# sam7x-nrf.net
KiCad netlist of a schematic drawn in EAGLE
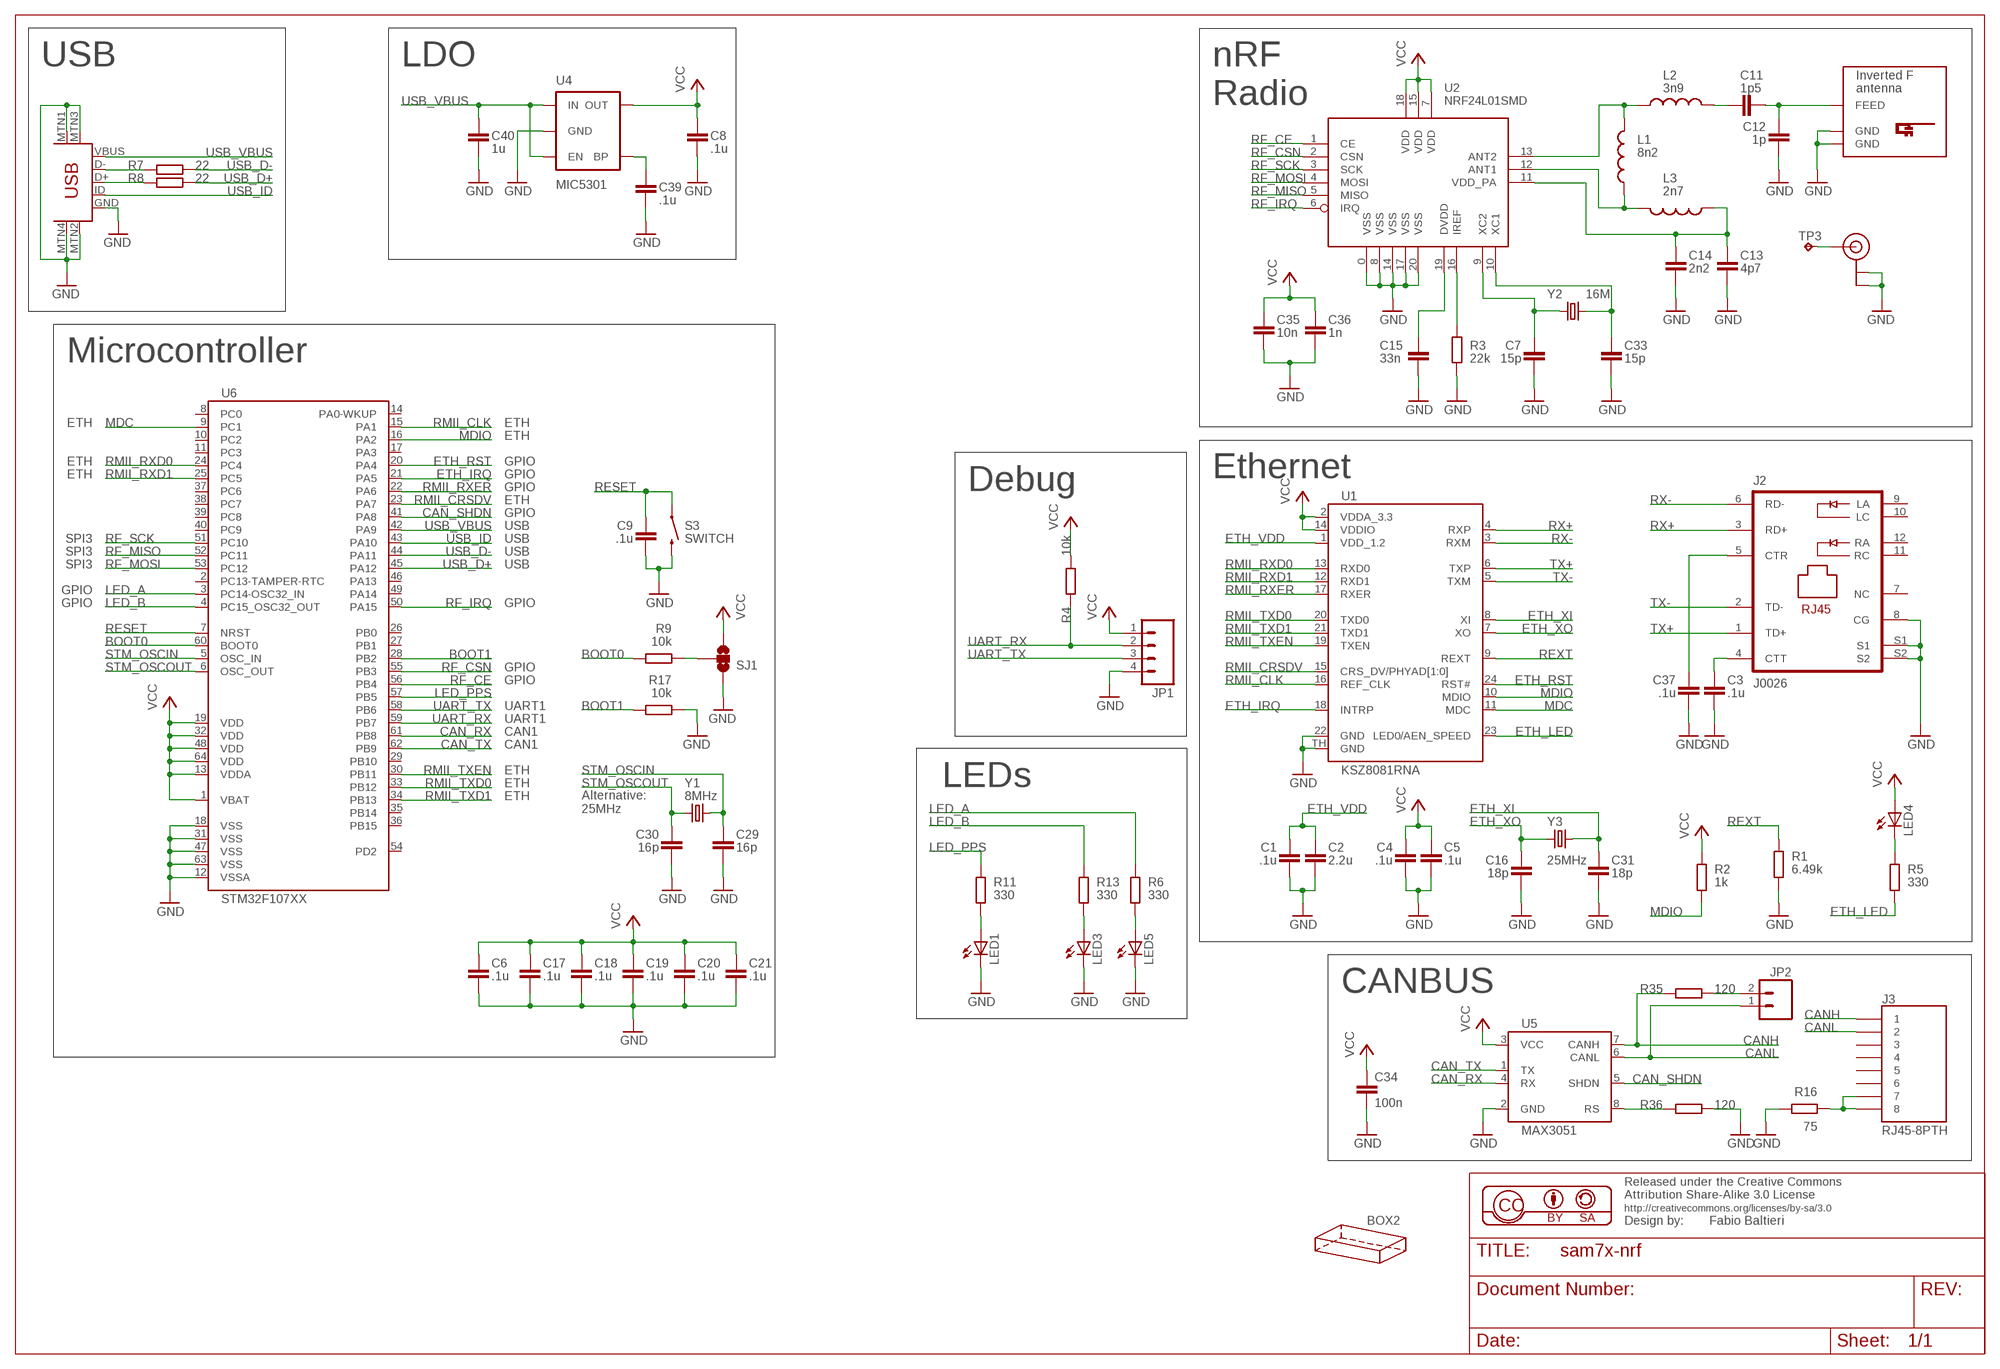
[diagram p0: schematic, sheet 1]

(export (version "E")
  (design (tool "Eeschema 10.0.6"))
  (components
    (comp (ref "BOX2")
      (value "HAMMOND-BOX-K")
      (footprint "eagle-import:1551K")
      (libsource (lib "eagle-import") (part "HAMMOND-BOX-K"))
    )
    (comp (ref "C1")
      (value ".1u")
      (footprint "eagle-import:C0603")
      (libsource (lib "eagle-import") (part "C-EUC0603"))
    )
    (comp (ref "C2")
      (value "2.2u")
      (footprint "eagle-import:C0603")
      (libsource (lib "eagle-import") (part "C-EUC0603"))
    )
    (comp (ref "C3")
      (value ".1u")
      (footprint "eagle-import:C0603")
      (libsource (lib "eagle-import") (part "C-EUC0603"))
    )
    (comp (ref "C4")
      (value ".1u")
      (footprint "eagle-import:C0603")
      (libsource (lib "eagle-import") (part "C-EUC0603"))
    )
    (comp (ref "C5")
      (value ".1u")
      (footprint "eagle-import:C0603")
      (libsource (lib "eagle-import") (part "C-EUC0603"))
    )
    (comp (ref "C6")
      (value ".1u")
      (footprint "eagle-import:C0603")
      (libsource (lib "eagle-import") (part "C-EUC0603"))
    )
    (comp (ref "C7")
      (value "15p")
      (footprint "eagle-import:C0603")
      (libsource (lib "eagle-import") (part "C-EUC0603"))
    )
    (comp (ref "C8")
      (value ".1u")
      (footprint "eagle-import:C0603")
      (libsource (lib "eagle-import") (part "C-EUC0603"))
    )
    (comp (ref "C9")
      (value ".1u")
      (footprint "eagle-import:C0603")
      (libsource (lib "eagle-import") (part "C-EUC0603"))
    )
    (comp (ref "C11")
      (value "1p5")
      (footprint "eagle-import:C0603")
      (libsource (lib "eagle-import") (part "C-EUC0603"))
    )
    (comp (ref "C12")
      (value "1p")
      (footprint "eagle-import:C0603")
      (libsource (lib "eagle-import") (part "C-EUC0603"))
    )
    (comp (ref "C13")
      (value "4p7")
      (footprint "eagle-import:C0603")
      (libsource (lib "eagle-import") (part "C-EUC0603"))
    )
    (comp (ref "C14")
      (value "2n2")
      (footprint "eagle-import:C0603")
      (libsource (lib "eagle-import") (part "C-EUC0603"))
    )
    (comp (ref "C15")
      (value "33n")
      (footprint "eagle-import:C0603")
      (libsource (lib "eagle-import") (part "C-EUC0603"))
    )
    (comp (ref "C16")
      (value "18p")
      (footprint "eagle-import:C0603")
      (libsource (lib "eagle-import") (part "C-EUC0603"))
    )
    (comp (ref "C17")
      (value ".1u")
      (footprint "eagle-import:C0603")
      (libsource (lib "eagle-import") (part "C-EUC0603"))
    )
    (comp (ref "C18")
      (value ".1u")
      (footprint "eagle-import:C0603")
      (libsource (lib "eagle-import") (part "C-EUC0603"))
    )
    (comp (ref "C19")
      (value ".1u")
      (footprint "eagle-import:C0603")
      (libsource (lib "eagle-import") (part "C-EUC0603"))
    )
    (comp (ref "C20")
      (value ".1u")
      (footprint "eagle-import:C0603")
      (libsource (lib "eagle-import") (part "C-EUC0603"))
    )
    (comp (ref "C21")
      (value ".1u")
      (footprint "eagle-import:C0603")
      (libsource (lib "eagle-import") (part "C-EUC0603"))
    )
    (comp (ref "C29")
      (value "16p")
      (footprint "eagle-import:C0603")
      (libsource (lib "eagle-import") (part "C-EUC0603"))
    )
    (comp (ref "C30")
      (value "16p")
      (footprint "eagle-import:C0603")
      (libsource (lib "eagle-import") (part "C-EUC0603"))
    )
    (comp (ref "C31")
      (value "18p")
      (footprint "eagle-import:C0603")
      (libsource (lib "eagle-import") (part "C-EUC0603"))
    )
    (comp (ref "C33")
      (value "15p")
      (footprint "eagle-import:C0603")
      (libsource (lib "eagle-import") (part "C-EUC0603"))
    )
    (comp (ref "C34")
      (value "100n")
      (footprint "eagle-import:C0603")
      (libsource (lib "eagle-import") (part "C-EUC0603"))
    )
    (comp (ref "C35")
      (value "10n")
      (footprint "eagle-import:C0603")
      (libsource (lib "eagle-import") (part "C-EUC0603"))
    )
    (comp (ref "C36")
      (value "1n")
      (footprint "eagle-import:C0603")
      (libsource (lib "eagle-import") (part "C-EUC0603"))
    )
    (comp (ref "C37")
      (value ".1u")
      (footprint "eagle-import:C0603")
      (libsource (lib "eagle-import") (part "C-EUC0603"))
    )
    (comp (ref "C39")
      (value ".1u")
      (footprint "eagle-import:C0603")
      (libsource (lib "eagle-import") (part "C-EUC0603"))
    )
    (comp (ref "C40")
      (value "1u")
      (footprint "eagle-import:C0603")
      (libsource (lib "eagle-import") (part "C-EUC0603"))
    )
    (comp (ref "J2")
      (value "J0026")
      (footprint "eagle-import:PJ-J0")
      (libsource (lib "eagle-import") (part "J0026"))
    )
    (comp (ref "J3")
      (value "RJ45-8PTH")
      (footprint "eagle-import:RJ45-8")
      (libsource (lib "eagle-import") (part "RJ45-8PTH"))
    )
    (comp (ref "JP1")
      (value "M04PTH")
      (footprint "eagle-import:1X04")
      (libsource (lib "eagle-import") (part "M04PTH"))
    )
    (comp (ref "JP2")
      (value "M02PTH")
      (footprint "eagle-import:1X02")
      (libsource (lib "eagle-import") (part "M02PTH"))
    )
    (comp (ref "L1")
      (value "8n2")
      (footprint "eagle-import:0603")
      (libsource (lib "eagle-import") (part "INDUCTOR0603"))
    )
    (comp (ref "L2")
      (value "3n9")
      (footprint "eagle-import:0603")
      (libsource (lib "eagle-import") (part "INDUCTOR0603"))
    )
    (comp (ref "L3")
      (value "2n7")
      (footprint "eagle-import:0603")
      (libsource (lib "eagle-import") (part "INDUCTOR0603"))
    )
    (comp (ref "LED1")
      (value "LEDCHIPLED_0805")
      (footprint "eagle-import:CHIPLED_0805")
      (libsource (lib "eagle-import") (part "LEDCHIPLED_0805"))
    )
    (comp (ref "LED3")
      (value "LEDCHIPLED_0805")
      (footprint "eagle-import:CHIPLED_0805")
      (libsource (lib "eagle-import") (part "LEDCHIPLED_0805"))
    )
    (comp (ref "LED4")
      (value "LEDCHIPLED_0805")
      (footprint "eagle-import:CHIPLED_0805")
      (libsource (lib "eagle-import") (part "LEDCHIPLED_0805"))
    )
    (comp (ref "LED5")
      (value "LEDCHIPLED_0805")
      (footprint "eagle-import:CHIPLED_0805")
      (libsource (lib "eagle-import") (part "LEDCHIPLED_0805"))
    )
    (comp (ref "R1")
      (value "6.49k")
      (footprint "eagle-import:R0603")
      (libsource (lib "eagle-import") (part "R-EU_R0603"))
    )
    (comp (ref "R2")
      (value "1k")
      (footprint "eagle-import:R0603")
      (libsource (lib "eagle-import") (part "R-EU_R0603"))
    )
    (comp (ref "R3")
      (value "22k")
      (footprint "eagle-import:R0603")
      (libsource (lib "eagle-import") (part "R-EU_R0603"))
    )
    (comp (ref "R4")
      (value "10k")
      (footprint "eagle-import:R0603")
      (libsource (lib "eagle-import") (part "R-EU_R0603"))
    )
    (comp (ref "R5")
      (value "330")
      (footprint "eagle-import:R0603")
      (libsource (lib "eagle-import") (part "R-EU_R0603"))
    )
    (comp (ref "R6")
      (value "330")
      (footprint "eagle-import:R0603")
      (libsource (lib "eagle-import") (part "R-EU_R0603"))
    )
    (comp (ref "R7")
      (value "22")
      (footprint "eagle-import:R0603")
      (libsource (lib "eagle-import") (part "R-EU_R0603"))
    )
    (comp (ref "R8")
      (value "22")
      (footprint "eagle-import:R0603")
      (libsource (lib "eagle-import") (part "R-EU_R0603"))
    )
    (comp (ref "R9")
      (value "10k")
      (footprint "eagle-import:R0603")
      (libsource (lib "eagle-import") (part "R-EU_R0603"))
    )
    (comp (ref "R11")
      (value "330")
      (footprint "eagle-import:R0603")
      (libsource (lib "eagle-import") (part "R-EU_R0603"))
    )
    (comp (ref "R13")
      (value "330")
      (footprint "eagle-import:R0603")
      (libsource (lib "eagle-import") (part "R-EU_R0603"))
    )
    (comp (ref "R16")
      (value "75")
      (footprint "eagle-import:R0805")
      (libsource (lib "eagle-import") (part "R-EU_R0805"))
    )
    (comp (ref "R17")
      (value "10k")
      (footprint "eagle-import:R0603")
      (libsource (lib "eagle-import") (part "R-EU_R0603"))
    )
    (comp (ref "R35")
      (value "120")
      (footprint "eagle-import:R0805")
      (libsource (lib "eagle-import") (part "R-EU_R0805"))
    )
    (comp (ref "R36")
      (value "120")
      (footprint "eagle-import:R0603")
      (libsource (lib "eagle-import") (part "R-EU_R0603"))
    )
    (comp (ref "S3")
      (value "SWITCH")
      (footprint "eagle-import:TACTILE_SWITCH_SMD")
      (libsource (lib "eagle-import") (part "SWITCH-MOMENTARY-2SMD"))
    )
    (comp (ref "SJ1")
      (value "SOLDERJUMPER_2WAYS")
      (footprint "eagle-import:SJ_3")
      (libsource (lib "eagle-import") (part "SOLDERJUMPER_2WAYS"))
    )
    (comp (ref "TP3")
      (value "TPTP08SQ")
      (footprint "eagle-import:TP08SQ")
      (libsource (lib "eagle-import") (part "TPTP08SQ"))
    )
    (comp (ref "U$4")
      (value "USB-MINIB-5PIN")
      (footprint "eagle-import:USB-MINIB")
      (libsource (lib "eagle-import") (part "USB-MINIB-5PIN"))
    )
    (comp (ref "U$5")
      (value "INVERTED_F_ANTENNA-2")
      (footprint "eagle-import:DN007-2")
      (libsource (lib "eagle-import") (part "INVERTED_F_ANTENNA-2"))
    )
    (comp (ref "U$6")
      (value "U.FL")
      (footprint "eagle-import:U.FL")
      (libsource (lib "eagle-import") (part "U.FL"))
    )
    (comp (ref "U1")
      (value "KSZ8081RNA")
      (footprint "eagle-import:QFN24")
      (libsource (lib "eagle-import") (part "KSZ8081"))
    )
    (comp (ref "U2")
      (value "NRF24L01SMD")
      (footprint "eagle-import:QFN20")
      (libsource (lib "eagle-import") (part "NRF24L01SMD"))
    )
    (comp (ref "U4")
      (value "MIC5301")
      (footprint "eagle-import:SOT23-5")
      (libsource (lib "eagle-import") (part "V_REG_LDOSMD"))
    )
    (comp (ref "U5")
      (value "MAX3051")
      (footprint "eagle-import:SO08")
      (libsource (lib "eagle-import") (part "MAX3051"))
    )
    (comp (ref "U6")
      (value "STM32F107XX")
      (footprint "eagle-import:LQFP64")
      (libsource (lib "eagle-import") (part "STM32F107XX"))
    )
    (comp (ref "Y1")
      (value "8MHz")
      (footprint "eagle-import:CRYSTAL-SMD-5X3")
      (libsource (lib "eagle-import") (part "CRYSTAL5X3"))
    )
    (comp (ref "Y2")
      (value "16M")
      (footprint "eagle-import:CRYSTAL-SMD-5X3")
      (libsource (lib "eagle-import") (part "CRYSTAL5X3"))
    )
    (comp (ref "Y3")
      (value "25MHz")
      (footprint "eagle-import:CRYSTAL-SMD-5X3")
      (libsource (lib "eagle-import") (part "CRYSTAL5X3"))
    )
  )
  (nets
    (net (code "1") (name "/BOOT0") (class "Default")
      (node (ref "R9") (pin "2") (pinfunction "2_2") (pintype "passive"))
      (node (ref "U6") (pin "60") (pinfunction "BOOT0_60") (pintype "bidirectional"))
    )
    (net (code "2") (name "/BOOT1") (class "Default")
      (node (ref "R17") (pin "2") (pinfunction "2_2") (pintype "passive"))
      (node (ref "U6") (pin "28") (pinfunction "PB2_28") (pintype "bidirectional"))
    )
    (net (code "3") (name "/CANH") (class "Default")
      (node (ref "J3") (pin "1") (pinfunction "1_1") (pintype "bidirectional"))
      (node (ref "R35") (pin "1") (pinfunction "1_1") (pintype "passive"))
      (node (ref "U5") (pin "7") (pinfunction "CANH_7") (pintype "bidirectional"))
    )
    (net (code "4") (name "/CANL") (class "Default")
      (node (ref "J3") (pin "2") (pinfunction "2_2") (pintype "bidirectional"))
      (node (ref "JP2") (pin "1") (pinfunction "1_1") (pintype "passive"))
      (node (ref "U5") (pin "6") (pinfunction "CANL_6") (pintype "bidirectional"))
    )
    (net (code "5") (name "/CAN_RX") (class "Default")
      (node (ref "U5") (pin "4") (pinfunction "RX_4") (pintype "bidirectional"))
      (node (ref "U6") (pin "61") (pinfunction "PB8_61") (pintype "bidirectional"))
    )
    (net (code "6") (name "/CAN_SHDN") (class "Default")
      (node (ref "U5") (pin "5") (pinfunction "SHDN_5") (pintype "bidirectional"))
      (node (ref "U6") (pin "41") (pinfunction "PA8_41") (pintype "bidirectional"))
    )
    (net (code "7") (name "/CAN_TX") (class "Default")
      (node (ref "U5") (pin "1") (pinfunction "TX_1") (pintype "bidirectional"))
      (node (ref "U6") (pin "62") (pinfunction "PB9_62") (pintype "bidirectional"))
    )
    (net (code "8") (name "/ETH_IRQ") (class "Default")
      (node (ref "U1") (pin "18") (pinfunction "INTRP_18") (pintype "bidirectional"))
      (node (ref "U6") (pin "21") (pinfunction "PA5_21") (pintype "bidirectional"))
    )
    (net (code "9") (name "/ETH_LED") (class "Default")
      (node (ref "R5") (pin "1") (pinfunction "1_1") (pintype "passive"))
      (node (ref "U1") (pin "23") (pinfunction "LED0/AEN_SPEED_23") (pintype "bidirectional"))
    )
    (net (code "10") (name "/ETH_RST") (class "Default")
      (node (ref "U1") (pin "24") (pinfunction "RST#_24") (pintype "bidirectional"))
      (node (ref "U6") (pin "20") (pinfunction "PA4_20") (pintype "bidirectional"))
    )
    (net (code "11") (name "/ETH_VDD") (class "Default")
      (node (ref "C1") (pin "1") (pinfunction "1_1") (pintype "passive"))
      (node (ref "C2") (pin "1") (pinfunction "1_1") (pintype "passive"))
      (node (ref "U1") (pin "1") (pinfunction "VDD_1.2_1") (pintype "bidirectional"))
    )
    (net (code "12") (name "/ETH_XI") (class "Default")
      (node (ref "C31") (pin "1") (pinfunction "1_1") (pintype "passive"))
      (node (ref "U1") (pin "8") (pinfunction "XI_8") (pintype "bidirectional"))
      (node (ref "Y3") (pin "3") (pinfunction "2_3") (pintype "passive"))
    )
    (net (code "13") (name "/ETH_XO") (class "Default")
      (node (ref "C16") (pin "1") (pinfunction "1_1") (pintype "passive"))
      (node (ref "U1") (pin "7") (pinfunction "XO_7") (pintype "bidirectional"))
      (node (ref "Y3") (pin "1") (pinfunction "1_1") (pintype "passive"))
    )
    (net (code "14") (name "/LED_A") (class "Default")
      (node (ref "R6") (pin "2") (pinfunction "2_2") (pintype "passive"))
      (node (ref "U6") (pin "3") (pinfunction "PC14-OSC32_IN_3") (pintype "bidirectional"))
    )
    (net (code "15") (name "/LED_B") (class "Default")
      (node (ref "R13") (pin "2") (pinfunction "2_2") (pintype "passive"))
      (node (ref "U6") (pin "4") (pinfunction "PC15_OSC32_OUT_4") (pintype "bidirectional"))
    )
    (net (code "16") (name "/LED_PPS") (class "Default")
      (node (ref "R11") (pin "2") (pinfunction "2_2") (pintype "passive"))
      (node (ref "U6") (pin "57") (pinfunction "PB5_57") (pintype "bidirectional"))
    )
    (net (code "17") (name "/MDC") (class "Default")
      (node (ref "U1") (pin "11") (pinfunction "MDC_11") (pintype "bidirectional"))
      (node (ref "U6") (pin "9") (pinfunction "PC1_9") (pintype "bidirectional"))
    )
    (net (code "18") (name "/MDIO") (class "Default")
      (node (ref "R2") (pin "1") (pinfunction "1_1") (pintype "passive"))
      (node (ref "U1") (pin "10") (pinfunction "MDIO_10") (pintype "bidirectional"))
      (node (ref "U6") (pin "16") (pinfunction "PA2_16") (pintype "bidirectional"))
    )
    (net (code "19") (name "/RESET") (class "Default")
      (node (ref "C9") (pin "1") (pinfunction "1_1") (pintype "passive"))
      (node (ref "S3") (pin "1") (pinfunction "1_1") (pintype "passive"))
      (node (ref "U6") (pin "7") (pinfunction "NRST_7") (pintype "bidirectional"))
    )
    (net (code "20") (name "/REXT") (class "Default")
      (node (ref "R1") (pin "2") (pinfunction "2_2") (pintype "passive"))
      (node (ref "U1") (pin "9") (pinfunction "REXT_9") (pintype "bidirectional"))
    )
    (net (code "21") (name "/RF_CE") (class "Default")
      (node (ref "U2") (pin "1") (pinfunction "CE_1") (pintype "input"))
      (node (ref "U6") (pin "56") (pinfunction "PB4_56") (pintype "bidirectional"))
    )
    (net (code "22") (name "/RF_CSN") (class "Default")
      (node (ref "U2") (pin "2") (pinfunction "CSN_2") (pintype "input"))
      (node (ref "U6") (pin "55") (pinfunction "PB3_55") (pintype "bidirectional"))
    )
    (net (code "23") (name "/RF_IRQ") (class "Default")
      (node (ref "U2") (pin "6") (pinfunction "IRQ_6") (pintype "output"))
      (node (ref "U6") (pin "50") (pinfunction "PA15_50") (pintype "bidirectional"))
    )
    (net (code "24") (name "/RF_MISO") (class "Default")
      (node (ref "U2") (pin "5") (pinfunction "MISO_5") (pintype "output"))
      (node (ref "U6") (pin "52") (pinfunction "PC11_52") (pintype "bidirectional"))
    )
    (net (code "25") (name "/RF_MOSI") (class "Default")
      (node (ref "U2") (pin "4") (pinfunction "MOSI_4") (pintype "input"))
      (node (ref "U6") (pin "53") (pinfunction "PC12_53") (pintype "bidirectional"))
    )
    (net (code "26") (name "/RF_SCK") (class "Default")
      (node (ref "U2") (pin "3") (pinfunction "SCK_3") (pintype "input"))
      (node (ref "U6") (pin "51") (pinfunction "PC10_51") (pintype "bidirectional"))
    )
    (net (code "27") (name "/RMII_CLK") (class "Default")
      (node (ref "U1") (pin "16") (pinfunction "REF_CLK_16") (pintype "bidirectional"))
      (node (ref "U6") (pin "15") (pinfunction "PA1_15") (pintype "bidirectional"))
    )
    (net (code "28") (name "/RMII_CRSDV") (class "Default")
      (node (ref "U1") (pin "15") (pinfunction "CRS_DV/PHYAD[1:0]_15") (pintype "bidirectional"))
      (node (ref "U6") (pin "23") (pinfunction "PA7_23") (pintype "bidirectional"))
    )
    (net (code "29") (name "/RMII_RXD0") (class "Default")
      (node (ref "U1") (pin "13") (pinfunction "RXD0_13") (pintype "bidirectional"))
      (node (ref "U6") (pin "24") (pinfunction "PC4_24") (pintype "bidirectional"))
    )
    (net (code "30") (name "/RMII_RXD1") (class "Default")
      (node (ref "U1") (pin "12") (pinfunction "RXD1_12") (pintype "bidirectional"))
      (node (ref "U6") (pin "25") (pinfunction "PC5_25") (pintype "bidirectional"))
    )
    (net (code "31") (name "/RMII_RXER") (class "Default")
      (node (ref "U1") (pin "17") (pinfunction "RXER_17") (pintype "bidirectional"))
      (node (ref "U6") (pin "22") (pinfunction "PA6_22") (pintype "bidirectional"))
    )
    (net (code "32") (name "/RMII_TXD0") (class "Default")
      (node (ref "U1") (pin "20") (pinfunction "TXD0_20") (pintype "bidirectional"))
      (node (ref "U6") (pin "33") (pinfunction "PB12_33") (pintype "bidirectional"))
    )
    (net (code "33") (name "/RMII_TXD1") (class "Default")
      (node (ref "U1") (pin "21") (pinfunction "TXD1_21") (pintype "bidirectional"))
      (node (ref "U6") (pin "34") (pinfunction "PB13_34") (pintype "bidirectional"))
    )
    (net (code "34") (name "/RMII_TXEN") (class "Default")
      (node (ref "U1") (pin "19") (pinfunction "TXEN_19") (pintype "bidirectional"))
      (node (ref "U6") (pin "30") (pinfunction "PB11_30") (pintype "bidirectional"))
    )
    (net (code "35") (name "/RX+") (class "Default")
      (node (ref "J2") (pin "3") (pinfunction "RD+_3") (pintype "bidirectional"))
      (node (ref "U1") (pin "4") (pinfunction "RXP_4") (pintype "bidirectional"))
    )
    (net (code "36") (name "/RX-") (class "Default")
      (node (ref "J2") (pin "6") (pinfunction "RD-_6") (pintype "bidirectional"))
      (node (ref "U1") (pin "3") (pinfunction "RXM_3") (pintype "bidirectional"))
    )
    (net (code "37") (name "/STM_OSCIN") (class "Default")
      (node (ref "C29") (pin "1") (pinfunction "1_1") (pintype "passive"))
      (node (ref "U6") (pin "5") (pinfunction "OSC_IN_5") (pintype "bidirectional"))
      (node (ref "Y1") (pin "3") (pinfunction "2_3") (pintype "passive"))
    )
    (net (code "38") (name "/STM_OSCOUT") (class "Default")
      (node (ref "C30") (pin "1") (pinfunction "1_1") (pintype "passive"))
      (node (ref "U6") (pin "6") (pinfunction "OSC_OUT_6") (pintype "bidirectional"))
      (node (ref "Y1") (pin "1") (pinfunction "1_1") (pintype "passive"))
    )
    (net (code "39") (name "/TX+") (class "Default")
      (node (ref "J2") (pin "1") (pinfunction "TD+_1") (pintype "bidirectional"))
      (node (ref "U1") (pin "6") (pinfunction "TXP_6") (pintype "bidirectional"))
    )
    (net (code "40") (name "/TX-") (class "Default")
      (node (ref "J2") (pin "2") (pinfunction "TD-_2") (pintype "bidirectional"))
      (node (ref "U1") (pin "5") (pinfunction "TXM_5") (pintype "bidirectional"))
    )
    (net (code "41") (name "/UART_RX") (class "Default")
      (node (ref "JP1") (pin "2") (pinfunction "2_2") (pintype "passive"))
      (node (ref "R4") (pin "1") (pinfunction "1_1") (pintype "passive"))
      (node (ref "U6") (pin "59") (pinfunction "PB7_59") (pintype "bidirectional"))
    )
    (net (code "42") (name "/UART_TX") (class "Default")
      (node (ref "JP1") (pin "3") (pinfunction "3_3") (pintype "passive"))
      (node (ref "U6") (pin "58") (pinfunction "PB6_58") (pintype "bidirectional"))
    )
    (net (code "43") (name "/USB_D+") (class "Default")
      (node (ref "R8") (pin "2") (pinfunction "2_2") (pintype "passive"))
      (node (ref "U6") (pin "45") (pinfunction "PA12_45") (pintype "bidirectional"))
    )
    (net (code "44") (name "/USB_D-") (class "Default")
      (node (ref "R7") (pin "2") (pinfunction "2_2") (pintype "passive"))
      (node (ref "U6") (pin "44") (pinfunction "PA11_44") (pintype "bidirectional"))
    )
    (net (code "45") (name "/USB_ID") (class "Default")
      (node (ref "U$4") (pin "ID") (pinfunction "ID_ID") (pintype "bidirectional"))
      (node (ref "U6") (pin "43") (pinfunction "PA10_43") (pintype "bidirectional"))
    )
    (net (code "46") (name "/USB_VBUS") (class "Default")
      (node (ref "C40") (pin "1") (pinfunction "1_1") (pintype "passive"))
      (node (ref "U$4") (pin "VBUS") (pinfunction "VBUS_VBUS") (pintype "bidirectional"))
      (node (ref "U4") (pin "1") (pinfunction "IN_1") (pintype "input"))
      (node (ref "U4") (pin "3") (pinfunction "EN_3") (pintype "input"))
      (node (ref "U6") (pin "42") (pinfunction "PA9_42") (pintype "bidirectional"))
    )
    (net (code "47") (name "GND") (class "Default")
      (node (ref "C1") (pin "2") (pinfunction "2_2") (pintype "passive"))
      (node (ref "C12") (pin "2") (pinfunction "2_2") (pintype "passive"))
      (node (ref "C13") (pin "2") (pinfunction "2_2") (pintype "passive"))
      (node (ref "C14") (pin "2") (pinfunction "2_2") (pintype "passive"))
      (node (ref "C15") (pin "2") (pinfunction "2_2") (pintype "passive"))
      (node (ref "C16") (pin "2") (pinfunction "2_2") (pintype "passive"))
      (node (ref "C17") (pin "2") (pinfunction "2_2") (pintype "passive"))
      (node (ref "C18") (pin "2") (pinfunction "2_2") (pintype "passive"))
      (node (ref "C19") (pin "2") (pinfunction "2_2") (pintype "passive"))
      (node (ref "C2") (pin "2") (pinfunction "2_2") (pintype "passive"))
      (node (ref "C20") (pin "2") (pinfunction "2_2") (pintype "passive"))
      (node (ref "C21") (pin "2") (pinfunction "2_2") (pintype "passive"))
      (node (ref "C29") (pin "2") (pinfunction "2_2") (pintype "passive"))
      (node (ref "C3") (pin "2") (pinfunction "2_2") (pintype "passive"))
      (node (ref "C30") (pin "2") (pinfunction "2_2") (pintype "passive"))
      (node (ref "C31") (pin "2") (pinfunction "2_2") (pintype "passive"))
      (node (ref "C33") (pin "2") (pinfunction "2_2") (pintype "passive"))
      (node (ref "C34") (pin "2") (pinfunction "2_2") (pintype "passive"))
      (node (ref "C35") (pin "2") (pinfunction "2_2") (pintype "passive"))
      (node (ref "C36") (pin "2") (pinfunction "2_2") (pintype "passive"))
      (node (ref "C37") (pin "2") (pinfunction "2_2") (pintype "passive"))
      (node (ref "C39") (pin "2") (pinfunction "2_2") (pintype "passive"))
      (node (ref "C4") (pin "2") (pinfunction "2_2") (pintype "passive"))
      (node (ref "C40") (pin "2") (pinfunction "2_2") (pintype "passive"))
      (node (ref "C5") (pin "2") (pinfunction "2_2") (pintype "passive"))
      (node (ref "C6") (pin "2") (pinfunction "2_2") (pintype "passive"))
      (node (ref "C7") (pin "2") (pinfunction "2_2") (pintype "passive"))
      (node (ref "C8") (pin "2") (pinfunction "2_2") (pintype "passive"))
      (node (ref "C9") (pin "2") (pinfunction "2_2") (pintype "passive"))
      (node (ref "J2") (pin "8") (pinfunction "CG_8") (pintype "passive"))
      (node (ref "J2") (pin "S1") (pinfunction "S1_S1") (pintype "passive"))
      (node (ref "J2") (pin "S2") (pinfunction "S2_S2") (pintype "passive"))
      (node (ref "JP1") (pin "4") (pinfunction "4_4") (pintype "passive"))
      (node (ref "LED1") (pin "C") (pinfunction "C_C") (pintype "passive"))
      (node (ref "LED3") (pin "C") (pinfunction "C_C") (pintype "passive"))
      (node (ref "LED5") (pin "C") (pinfunction "C_C") (pintype "passive"))
      (node (ref "R1") (pin "1") (pinfunction "1_1") (pintype "passive"))
      (node (ref "R16") (pin "1") (pinfunction "1_1") (pintype "passive"))
      (node (ref "R17") (pin "1") (pinfunction "1_1") (pintype "passive"))
      (node (ref "R3") (pin "2") (pinfunction "2_2") (pintype "passive"))
      (node (ref "R36") (pin "2") (pinfunction "2_2") (pintype "passive"))
      (node (ref "S3") (pin "3") (pinfunction "2_3") (pintype "passive"))
      (node (ref "SJ1") (pin "1") (pinfunction "1_1") (pintype "passive"))
      (node (ref "U$4") (pin "GND") (pinfunction "GND_GND") (pintype "bidirectional"))
      (node (ref "U$4") (pin "MTN1") (pinfunction "MTN2_MTN1") (pintype "bidirectional"))
      (node (ref "U$4") (pin "MTN2") (pinfunction "MTN3_MTN2") (pintype "bidirectional"))
      (node (ref "U$4") (pin "MTN3") (pinfunction "MTN1_MTN3") (pintype "bidirectional"))
      (node (ref "U$4") (pin "MTN4") (pinfunction "MTN4_MTN4") (pintype "bidirectional"))
      (node (ref "U$5") (pin "GND") (pinfunction "GND_GND") (pintype "bidirectional"))
      (node (ref "U$5") (pin "GND@1") (pinfunction "GND_GND@1") (pintype "bidirectional"))
      (node (ref "U$6") (pin "P$1") (pinfunction "GND_P$1") (pintype "bidirectional"))
      (node (ref "U$6") (pin "P$2") (pinfunction "GND_P$2") (pintype "bidirectional"))
      (node (ref "U1") (pin "22") (pinfunction "GND_22") (pintype "bidirectional"))
      (node (ref "U1") (pin "TH") (pinfunction "GND_TH") (pintype "bidirectional"))
      (node (ref "U2") (pin "0") (pinfunction "VSS_0") (pintype "power_in"))
      (node (ref "U2") (pin "14") (pinfunction "VSS_14") (pintype "power_in"))
      (node (ref "U2") (pin "17") (pinfunction "VSS_17") (pintype "power_in"))
      (node (ref "U2") (pin "20") (pinfunction "VSS_20") (pintype "power_in"))
      (node (ref "U2") (pin "8") (pinfunction "VSS_8") (pintype "power_in"))
      (node (ref "U4") (pin "2") (pinfunction "GND_2") (pintype "input"))
      (node (ref "U5") (pin "2") (pinfunction "GND_2") (pintype "bidirectional"))
      (node (ref "U6") (pin "12") (pinfunction "VSSA_12") (pintype "bidirectional"))
      (node (ref "U6") (pin "18") (pinfunction "VSS_18") (pintype "bidirectional"))
      (node (ref "U6") (pin "31") (pinfunction "VSS_31") (pintype "bidirectional"))
      (node (ref "U6") (pin "47") (pinfunction "VSS_47") (pintype "bidirectional"))
      (node (ref "U6") (pin "63") (pinfunction "VSS_63") (pintype "bidirectional"))
    )
    (net (code "48") (name "Net-(C11-Pad1)") (class "Default")
      (node (ref "C11") (pin "1") (pinfunction "1_1") (pintype "passive"))
      (node (ref "L2") (pin "2") (pinfunction "2_2") (pintype "passive"))
    )
    (net (code "49") (name "Net-(C11-Pad2)") (class "Default")
      (node (ref "C11") (pin "2") (pinfunction "2_2") (pintype "passive"))
      (node (ref "C12") (pin "1") (pinfunction "1_1") (pintype "passive"))
      (node (ref "U$5") (pin "FEED") (pinfunction "FEED_FEED") (pintype "bidirectional"))
    )
    (net (code "50") (name "Net-(J2-CTR)") (class "Default")
      (node (ref "C37") (pin "1") (pinfunction "1_1") (pintype "passive"))
      (node (ref "J2") (pin "5") (pinfunction "CTR_5") (pintype "bidirectional"))
    )
    (net (code "51") (name "Net-(J2-CTT)") (class "Default")
      (node (ref "C3") (pin "1") (pinfunction "1_1") (pintype "passive"))
      (node (ref "J2") (pin "4") (pinfunction "CTT_4") (pintype "bidirectional"))
    )
    (net (code "52") (name "Net-(J3-Pad7)") (class "Default")
      (node (ref "J3") (pin "7") (pinfunction "7_7") (pintype "bidirectional"))
      (node (ref "J3") (pin "8") (pinfunction "8_8") (pintype "bidirectional"))
      (node (ref "R16") (pin "2") (pinfunction "2_2") (pintype "passive"))
    )
    (net (code "53") (name "Net-(JP2-Pad2)") (class "Default")
      (node (ref "JP2") (pin "2") (pinfunction "2_2") (pintype "passive"))
      (node (ref "R35") (pin "2") (pinfunction "2_2") (pintype "passive"))
    )
    (net (code "54") (name "Net-(LED1-PadA)") (class "Default")
      (node (ref "LED1") (pin "A") (pinfunction "A_A") (pintype "passive"))
      (node (ref "R11") (pin "1") (pinfunction "1_1") (pintype "passive"))
    )
    (net (code "55") (name "Net-(LED3-PadA)") (class "Default")
      (node (ref "LED3") (pin "A") (pinfunction "A_A") (pintype "passive"))
      (node (ref "R13") (pin "1") (pinfunction "1_1") (pintype "passive"))
    )
    (net (code "56") (name "Net-(LED4-PadC)") (class "Default")
      (node (ref "LED4") (pin "C") (pinfunction "C_C") (pintype "passive"))
      (node (ref "R5") (pin "2") (pinfunction "2_2") (pintype "passive"))
    )
    (net (code "57") (name "Net-(LED5-PadA)") (class "Default")
      (node (ref "LED5") (pin "A") (pinfunction "A_A") (pintype "passive"))
      (node (ref "R6") (pin "1") (pinfunction "1_1") (pintype "passive"))
    )
    (net (code "58") (name "Net-(R7-Pad1)") (class "Default")
      (node (ref "R7") (pin "1") (pinfunction "1_1") (pintype "passive"))
      (node (ref "U$4") (pin "D-") (pinfunction "D-_D-") (pintype "bidirectional"))
    )
    (net (code "59") (name "Net-(R8-Pad1)") (class "Default")
      (node (ref "R8") (pin "1") (pinfunction "1_1") (pintype "passive"))
      (node (ref "U$4") (pin "D+") (pinfunction "D+_D+") (pintype "bidirectional"))
    )
    (net (code "60") (name "Net-(R9-Pad1)") (class "Default")
      (node (ref "R9") (pin "1") (pinfunction "1_1") (pintype "passive"))
      (node (ref "SJ1") (pin "2") (pinfunction "2_2") (pintype "passive"))
    )
    (net (code "61") (name "Net-(U$6-SIGNAL)") (class "Default")
      (node (ref "TP3") (pin "TP") (pinfunction "TP_TP") (pintype "input"))
      (node (ref "U$6") (pin "P$3") (pinfunction "SIGNAL_P$3") (pintype "bidirectional"))
    )
    (net (code "62") (name "Net-(U2-ANT1)") (class "Default")
      (node (ref "L1") (pin "2") (pinfunction "2_2") (pintype "passive"))
      (node (ref "L3") (pin "2") (pinfunction "2_2") (pintype "passive"))
      (node (ref "U2") (pin "12") (pinfunction "ANT1_12") (pintype "output"))
    )
    (net (code "63") (name "Net-(U2-ANT2)") (class "Default")
      (node (ref "L1") (pin "1") (pinfunction "1_1") (pintype "passive"))
      (node (ref "L2") (pin "1") (pinfunction "1_1") (pintype "passive"))
      (node (ref "U2") (pin "13") (pinfunction "ANT2_13") (pintype "output"))
    )
    (net (code "64") (name "Net-(U2-DVDD)") (class "Default")
      (node (ref "C15") (pin "1") (pinfunction "1_1") (pintype "passive"))
      (node (ref "U2") (pin "19") (pinfunction "DVDD_19") (pintype "power_in"))
    )
    (net (code "65") (name "Net-(U2-IREF)") (class "Default")
      (node (ref "R3") (pin "1") (pinfunction "1_1") (pintype "passive"))
      (node (ref "U2") (pin "16") (pinfunction "IREF_16") (pintype "input"))
    )
    (net (code "66") (name "Net-(U2-VDD_PA)") (class "Default")
      (node (ref "C13") (pin "1") (pinfunction "1_1") (pintype "passive"))
      (node (ref "C14") (pin "1") (pinfunction "1_1") (pintype "passive"))
      (node (ref "L3") (pin "1") (pinfunction "1_1") (pintype "passive"))
      (node (ref "U2") (pin "11") (pinfunction "VDD_PA_11") (pintype "power_in"))
    )
    (net (code "67") (name "Net-(U2-XC1)") (class "Default")
      (node (ref "C33") (pin "1") (pinfunction "1_1") (pintype "passive"))
      (node (ref "U2") (pin "10") (pinfunction "XC1_10") (pintype "input"))
      (node (ref "Y2") (pin "3") (pinfunction "2_3") (pintype "passive"))
    )
    (net (code "68") (name "Net-(U2-XC2)") (class "Default")
      (node (ref "C7") (pin "1") (pinfunction "1_1") (pintype "passive"))
      (node (ref "U2") (pin "9") (pinfunction "XC2_9") (pintype "input"))
      (node (ref "Y2") (pin "1") (pinfunction "1_1") (pintype "passive"))
    )
    (net (code "69") (name "Net-(U4-BP)") (class "Default")
      (node (ref "C39") (pin "1") (pinfunction "1_1") (pintype "passive"))
      (node (ref "U4") (pin "4") (pinfunction "BP_4") (pintype "input"))
    )
    (net (code "70") (name "Net-(U5-RS)") (class "Default")
      (node (ref "R36") (pin "1") (pinfunction "1_1") (pintype "passive"))
      (node (ref "U5") (pin "8") (pinfunction "RS_8") (pintype "bidirectional"))
    )
    (net (code "71") (name "VCC") (class "Default")
      (node (ref "C17") (pin "1") (pinfunction "1_1") (pintype "passive"))
      (node (ref "C18") (pin "1") (pinfunction "1_1") (pintype "passive"))
      (node (ref "C19") (pin "1") (pinfunction "1_1") (pintype "passive"))
      (node (ref "C20") (pin "1") (pinfunction "1_1") (pintype "passive"))
      (node (ref "C21") (pin "1") (pinfunction "1_1") (pintype "passive"))
      (node (ref "C34") (pin "1") (pinfunction "1_1") (pintype "passive"))
      (node (ref "C35") (pin "1") (pinfunction "1_1") (pintype "passive"))
      (node (ref "C36") (pin "1") (pinfunction "1_1") (pintype "passive"))
      (node (ref "C4") (pin "1") (pinfunction "1_1") (pintype "passive"))
      (node (ref "C5") (pin "1") (pinfunction "1_1") (pintype "passive"))
      (node (ref "C6") (pin "1") (pinfunction "1_1") (pintype "passive"))
      (node (ref "C8") (pin "1") (pinfunction "1_1") (pintype "passive"))
      (node (ref "JP1") (pin "1") (pinfunction "1_1") (pintype "passive"))
      (node (ref "LED4") (pin "A") (pinfunction "A_A") (pintype "passive"))
      (node (ref "R2") (pin "2") (pinfunction "2_2") (pintype "passive"))
      (node (ref "R4") (pin "2") (pinfunction "2_2") (pintype "passive"))
      (node (ref "SJ1") (pin "3") (pinfunction "3_3") (pintype "passive"))
      (node (ref "U1") (pin "14") (pinfunction "VDDIO_14") (pintype "bidirectional"))
      (node (ref "U1") (pin "2") (pinfunction "VDDA_3.3_2") (pintype "bidirectional"))
      (node (ref "U2") (pin "15") (pinfunction "VDD_15") (pintype "power_in"))
      (node (ref "U2") (pin "18") (pinfunction "VDD_18") (pintype "power_in"))
      (node (ref "U2") (pin "7") (pinfunction "VDD_7") (pintype "power_in"))
      (node (ref "U4") (pin "5") (pinfunction "OUT_5") (pintype "passive"))
      (node (ref "U5") (pin "3") (pinfunction "VCC_3") (pintype "bidirectional"))
      (node (ref "U6") (pin "1") (pinfunction "VBAT_1") (pintype "bidirectional"))
      (node (ref "U6") (pin "13") (pinfunction "VDDA_13") (pintype "bidirectional"))
      (node (ref "U6") (pin "19") (pinfunction "VDD_19") (pintype "bidirectional"))
      (node (ref "U6") (pin "32") (pinfunction "VDD_32") (pintype "bidirectional"))
      (node (ref "U6") (pin "48") (pinfunction "VDD_48") (pintype "bidirectional"))
      (node (ref "U6") (pin "64") (pinfunction "VDD_64") (pintype "bidirectional"))
    )
    (net (code "72") (name "unconnected-(J2-LA-Pad9)") (class "Default")
      (node (ref "J2") (pin "9") (pinfunction "LA_9") (pintype "passive"))
    )
    (net (code "73") (name "unconnected-(J2-LC-Pad10)") (class "Default")
      (node (ref "J2") (pin "10") (pinfunction "LC_10") (pintype "passive"))
    )
    (net (code "74") (name "unconnected-(J2-NC-Pad7)") (class "Default")
      (node (ref "J2") (pin "7") (pinfunction "NC_7") (pintype "passive"))
    )
    (net (code "75") (name "unconnected-(J2-RA-Pad12)") (class "Default")
      (node (ref "J2") (pin "12") (pinfunction "RA_12") (pintype "passive"))
    )
    (net (code "76") (name "unconnected-(J2-RC-Pad11)") (class "Default")
      (node (ref "J2") (pin "11") (pinfunction "RC_11") (pintype "passive"))
    )
    (net (code "77") (name "unconnected-(J3-Pad3)") (class "Default")
      (node (ref "J3") (pin "3") (pinfunction "3_3") (pintype "bidirectional"))
    )
    (net (code "78") (name "unconnected-(J3-Pad4)") (class "Default")
      (node (ref "J3") (pin "4") (pinfunction "4_4") (pintype "bidirectional"))
    )
    (net (code "79") (name "unconnected-(J3-Pad5)") (class "Default")
      (node (ref "J3") (pin "5") (pinfunction "5_5") (pintype "bidirectional"))
    )
    (net (code "80") (name "unconnected-(J3-Pad6)") (class "Default")
      (node (ref "J3") (pin "6") (pinfunction "6_6") (pintype "bidirectional"))
    )
    (net (code "81") (name "unconnected-(U6-PA0-WKUP-Pad14)") (class "Default")
      (node (ref "U6") (pin "14") (pinfunction "PA0-WKUP_14") (pintype "bidirectional"))
    )
    (net (code "82") (name "unconnected-(U6-PA3-Pad17)") (class "Default")
      (node (ref "U6") (pin "17") (pinfunction "PA3_17") (pintype "bidirectional"))
    )
    (net (code "83") (name "unconnected-(U6-PA13-Pad46)") (class "Default")
      (node (ref "U6") (pin "46") (pinfunction "PA13_46") (pintype "bidirectional"))
    )
    (net (code "84") (name "unconnected-(U6-PA14-Pad49)") (class "Default")
      (node (ref "U6") (pin "49") (pinfunction "PA14_49") (pintype "bidirectional"))
    )
    (net (code "85") (name "unconnected-(U6-PB0-Pad26)") (class "Default")
      (node (ref "U6") (pin "26") (pinfunction "PB0_26") (pintype "bidirectional"))
    )
    (net (code "86") (name "unconnected-(U6-PB1-Pad27)") (class "Default")
      (node (ref "U6") (pin "27") (pinfunction "PB1_27") (pintype "bidirectional"))
    )
    (net (code "87") (name "unconnected-(U6-PB10-Pad29)") (class "Default")
      (node (ref "U6") (pin "29") (pinfunction "PB10_29") (pintype "bidirectional"))
    )
    (net (code "88") (name "unconnected-(U6-PB14-Pad35)") (class "Default")
      (node (ref "U6") (pin "35") (pinfunction "PB14_35") (pintype "bidirectional"))
    )
    (net (code "89") (name "unconnected-(U6-PB15-Pad36)") (class "Default")
      (node (ref "U6") (pin "36") (pinfunction "PB15_36") (pintype "bidirectional"))
    )
    (net (code "90") (name "unconnected-(U6-PC0-Pad8)") (class "Default")
      (node (ref "U6") (pin "8") (pinfunction "PC0_8") (pintype "bidirectional"))
    )
    (net (code "91") (name "unconnected-(U6-PC2-Pad10)") (class "Default")
      (node (ref "U6") (pin "10") (pinfunction "PC2_10") (pintype "bidirectional"))
    )
    (net (code "92") (name "unconnected-(U6-PC3-Pad11)") (class "Default")
      (node (ref "U6") (pin "11") (pinfunction "PC3_11") (pintype "bidirectional"))
    )
    (net (code "93") (name "unconnected-(U6-PC6-Pad37)") (class "Default")
      (node (ref "U6") (pin "37") (pinfunction "PC6_37") (pintype "bidirectional"))
    )
    (net (code "94") (name "unconnected-(U6-PC7-Pad38)") (class "Default")
      (node (ref "U6") (pin "38") (pinfunction "PC7_38") (pintype "bidirectional"))
    )
    (net (code "95") (name "unconnected-(U6-PC8-Pad39)") (class "Default")
      (node (ref "U6") (pin "39") (pinfunction "PC8_39") (pintype "bidirectional"))
    )
    (net (code "96") (name "unconnected-(U6-PC9-Pad40)") (class "Default")
      (node (ref "U6") (pin "40") (pinfunction "PC9_40") (pintype "bidirectional"))
    )
    (net (code "97") (name "unconnected-(U6-PC13-TAMPER-RTC-Pad2)") (class "Default")
      (node (ref "U6") (pin "2") (pinfunction "PC13-TAMPER-RTC_2") (pintype "bidirectional"))
    )
    (net (code "98") (name "unconnected-(U6-PD2-Pad54)") (class "Default")
      (node (ref "U6") (pin "54") (pinfunction "PD2_54") (pintype "bidirectional"))
    )
  )
)
